# Gesture_rf_controller_v1.net
KiCad netlist of a schematic drawn in EAGLE
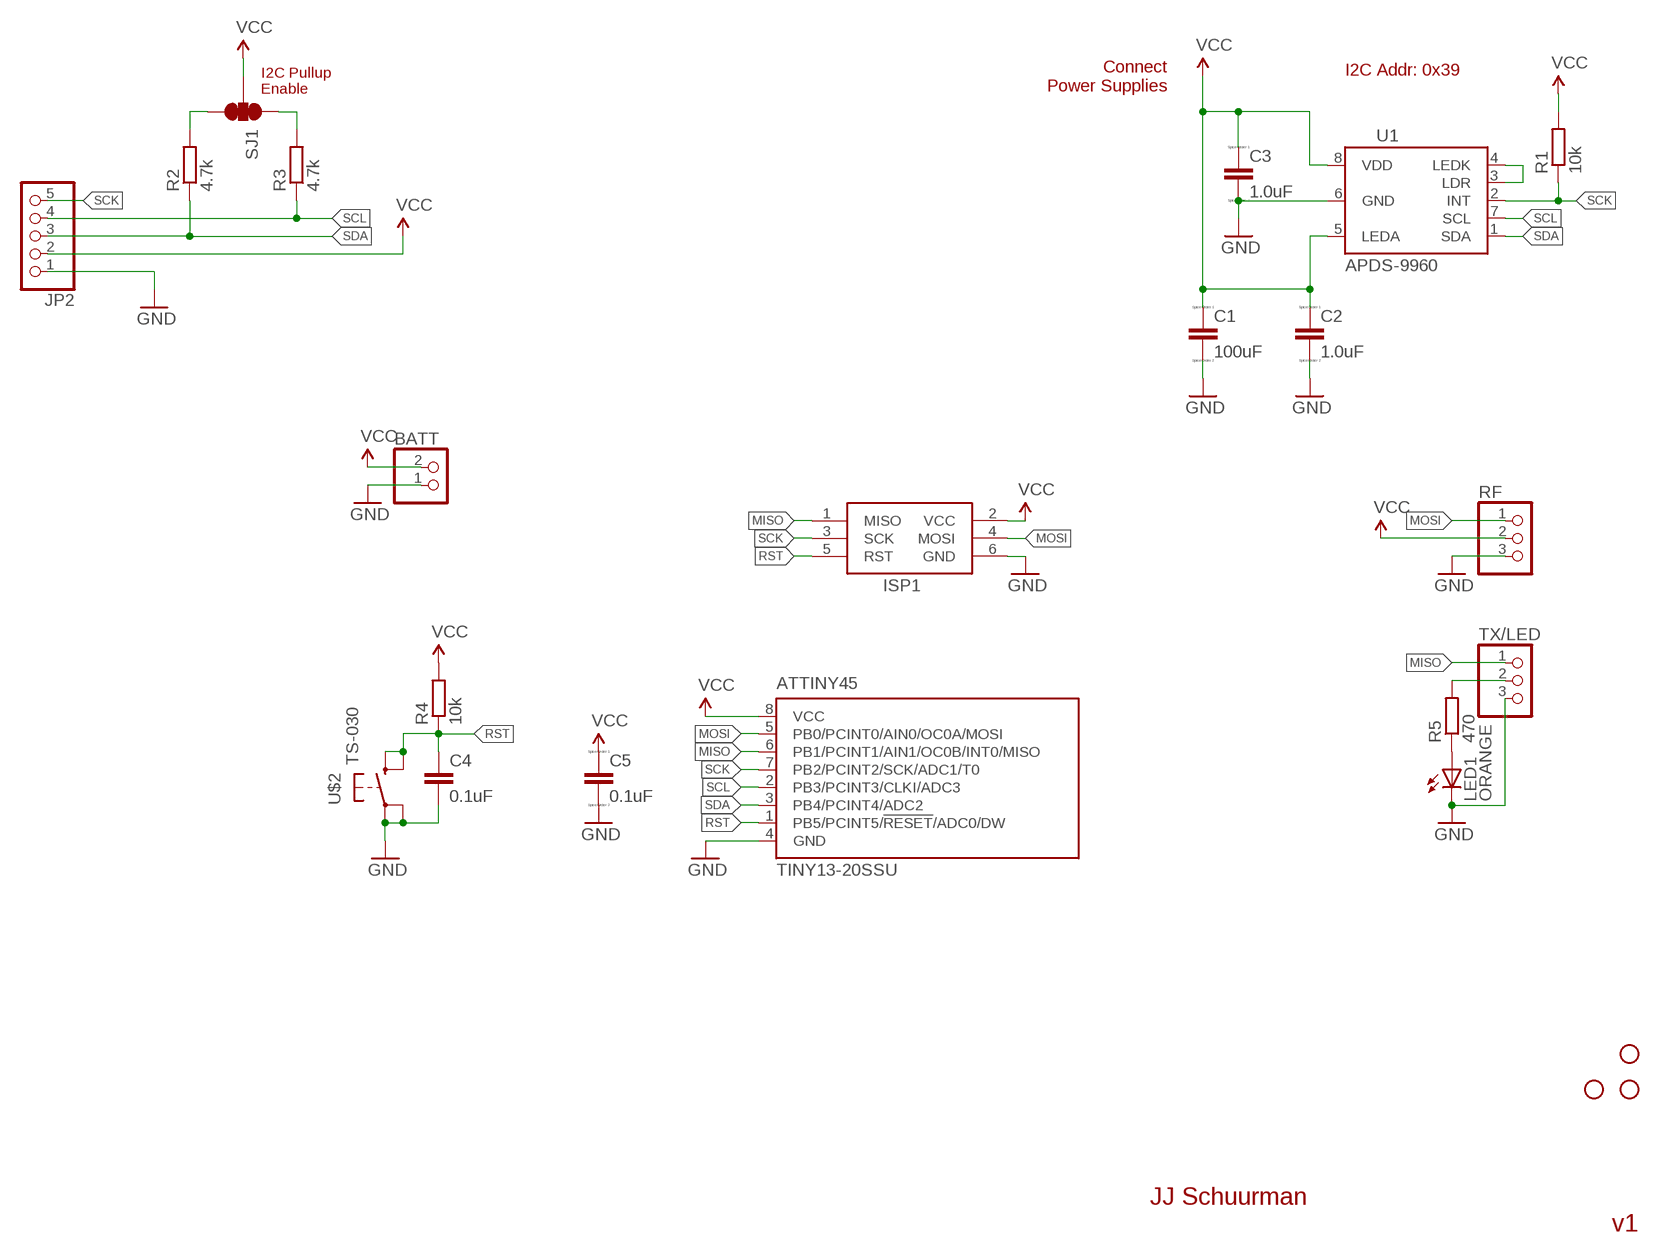
[diagram p0: schematic, sheet 1]

(export (version "E")
  (design (tool "Eeschema 10.0.6"))
  (components
    (comp (ref "ATTINY45")
      (value "TINY13-20SSU")
      (footprint "eagle-import:8S1")
      (fields (field (name "MPN") "ATTINY13-20SSU"))
      (libsource (lib "eagle-import") (part "TINY13SSU-20"))
    )
    (comp (ref "BATT")
      (value "JST_2PIN-THM")
      (footprint "eagle-import:JST-PH-2-THM")
      (libsource (lib "eagle-import") (part "JST_2PIN-THM"))
    )
    (comp (ref "C1")
      (value "100uF")
      (footprint "eagle-import:C0805")
      (libsource (lib "eagle-import") (part "resistor_C-EUC0805"))
    )
    (comp (ref "C2")
      (value "1.0uF")
      (footprint "eagle-import:C0805")
      (libsource (lib "eagle-import") (part "resistor_C-EUC0805"))
    )
    (comp (ref "C3")
      (value "1.0uF")
      (footprint "eagle-import:C0805")
      (libsource (lib "eagle-import") (part "resistor_C-EUC0805"))
    )
    (comp (ref "C4")
      (value "0.1uF")
      (footprint "eagle-import:C1206")
      (libsource (lib "eagle-import") (part "C-EUC1206"))
    )
    (comp (ref "C5")
      (value "0.1uF")
      (footprint "eagle-import:C0805")
      (libsource (lib "eagle-import") (part "resistor_C-EUC0805"))
    )
    (comp (ref "ISP1")
      (value "AVRISP-6")
      (footprint "eagle-import:AVRISP")
      (libsource (lib "eagle-import") (part "AVRISP-6"))
    )
    (comp (ref "JP2")
      (value "PINHD-1X5")
      (footprint "eagle-import:1X05")
      (libsource (lib "eagle-import") (part "PINHD-1X5"))
    )
    (comp (ref "LED1")
      (value "ORANGE")
      (footprint "eagle-import:CHIP-LED0805")
      (libsource (lib "eagle-import") (part "LEDCHIP-LED0805"))
    )
    (comp (ref "R1")
      (value "10k")
      (footprint "eagle-import:R0805")
      (libsource (lib "eagle-import") (part "R-EU_R0805"))
    )
    (comp (ref "R2")
      (value "4.7k")
      (footprint "eagle-import:R1206")
      (libsource (lib "eagle-import") (part "R-EU_R1206"))
    )
    (comp (ref "R3")
      (value "4.7k")
      (footprint "eagle-import:R1206")
      (libsource (lib "eagle-import") (part "R-EU_R1206"))
    )
    (comp (ref "R4")
      (value "10k")
      (footprint "eagle-import:M0805")
      (libsource (lib "eagle-import") (part "R-EU_M0805"))
    )
    (comp (ref "R5")
      (value "470")
      (footprint "eagle-import:R0805")
      (libsource (lib "eagle-import") (part "R-EU_R0805"))
    )
    (comp (ref "RF")
      (value "PINHD-1X3")
      (footprint "eagle-import:1X03")
      (libsource (lib "eagle-import") (part "PINHD-1X3"))
    )
    (comp (ref "SJ1")
      (value "SOLDERJUMPER_2WAYPASTE1&2&3")
      (footprint "eagle-import:SJ_3_PASTE1&2&3")
      (libsource (lib "eagle-import") (part "SOLDERJUMPER_2WAYPASTE1&2&3"))
    )
    (comp (ref "STANDOFF1")
      (value "STAND-OFF")
      (footprint "eagle-import:STAND-OFF")
      (libsource (lib "eagle-import") (part "STAND-OFF"))
    )
    (comp (ref "STANDOFF2")
      (value "STAND-OFF")
      (footprint "eagle-import:STAND-OFF")
      (libsource (lib "eagle-import") (part "STAND-OFF"))
    )
    (comp (ref "STANDOFF4")
      (value "STAND-OFF")
      (footprint "eagle-import:STAND-OFF")
      (libsource (lib "eagle-import") (part "STAND-OFF"))
    )
    (comp (ref "TX/LED")
      (value "PINHD-1X3")
      (footprint "eagle-import:1X03")
      (libsource (lib "eagle-import") (part "PINHD-1X3"))
    )
    (comp (ref "U$2")
      (value "TS-030")
      (footprint "eagle-import:TS-030")
      (libsource (lib "eagle-import") (part "TS-030"))
    )
    (comp (ref "U1")
      (value "APDS-9960")
      (footprint "eagle-import:APDS-9960")
      (libsource (lib "eagle-import") (part "APDS-9960"))
    )
  )
  (nets
    (net (code "1") (name "GND") (class "Default")
      (node (ref "ATTINY45") (pin "4") (pinfunction "GND_4") (pintype "power_in"))
      (node (ref "BATT") (pin "1") (pinfunction "2_1") (pintype "passive"))
      (node (ref "C1") (pin "2") (pinfunction "2_2") (pintype "passive"))
      (node (ref "C2") (pin "2") (pinfunction "2_2") (pintype "passive"))
      (node (ref "C3") (pin "2") (pinfunction "2_2") (pintype "passive"))
      (node (ref "C4") (pin "2") (pinfunction "2_2") (pintype "passive"))
      (node (ref "C5") (pin "2") (pinfunction "2_2") (pintype "passive"))
      (node (ref "ISP1") (pin "6") (pinfunction "GND_6") (pintype "power_in"))
      (node (ref "JP2") (pin "1") (pinfunction "1_1") (pintype "passive"))
      (node (ref "LED1") (pin "C") (pinfunction "C_C") (pintype "passive"))
      (node (ref "RF") (pin "3") (pinfunction "3_3") (pintype "passive"))
      (node (ref "TX/LED") (pin "3") (pinfunction "3_3") (pintype "passive"))
      (node (ref "U$2") (pin "P$2") (pinfunction "1_P$2") (pintype "passive"))
      (node (ref "U$2") (pin "P$3") (pinfunction "2_P$3") (pintype "passive"))
      (node (ref "U1") (pin "6") (pinfunction "GND_6") (pintype "bidirectional"))
    )
    (net (code "2") (name "MISO") (class "Default")
      (node (ref "ATTINY45") (pin "6") (pinfunction "PB1/PCINT1/AIN1/OC0B/INT0/MISO_6") (pintype "bidirectional"))
      (node (ref "ISP1") (pin "1") (pinfunction "MISO_1") (pintype "input"))
      (node (ref "TX/LED") (pin "1") (pinfunction "1_1") (pintype "passive"))
    )
    (net (code "3") (name "MOSI") (class "Default")
      (node (ref "ATTINY45") (pin "5") (pinfunction "PB0/PCINT0/AIN0/OC0A/MOSI_5") (pintype "bidirectional"))
      (node (ref "ISP1") (pin "4") (pinfunction "MOSI_4") (pintype "output"))
      (node (ref "RF") (pin "1") (pinfunction "1_1") (pintype "passive"))
    )
    (net (code "4") (name "Net-(LED1-PadA)") (class "Default")
      (node (ref "LED1") (pin "A") (pinfunction "A_A") (pintype "passive"))
      (node (ref "R5") (pin "1") (pinfunction "1_1") (pintype "passive"))
    )
    (net (code "5") (name "Net-(R2-Pad2)") (class "Default")
      (node (ref "R2") (pin "2") (pinfunction "2_2") (pintype "passive"))
      (node (ref "SJ1") (pin "3") (pinfunction "3_3") (pintype "passive"))
    )
    (net (code "6") (name "Net-(R3-Pad2)") (class "Default")
      (node (ref "R3") (pin "2") (pinfunction "2_2") (pintype "passive"))
      (node (ref "SJ1") (pin "1") (pinfunction "1_1") (pintype "passive"))
    )
    (net (code "7") (name "Net-(R5-Pad2)") (class "Default")
      (node (ref "R5") (pin "2") (pinfunction "2_2") (pintype "passive"))
      (node (ref "TX/LED") (pin "2") (pinfunction "2_2") (pintype "passive"))
    )
    (net (code "8") (name "Net-(U1-LDR)") (class "Default")
      (node (ref "U1") (pin "3") (pinfunction "LDR_3") (pintype "bidirectional"))
      (node (ref "U1") (pin "4") (pinfunction "LEDK_4") (pintype "bidirectional"))
    )
    (net (code "9") (name "RST") (class "Default")
      (node (ref "ATTINY45") (pin "1") (pinfunction "PB5/PCINT5/~{RESET}/ADC0/DW_1") (pintype "bidirectional"))
      (node (ref "C4") (pin "1") (pinfunction "1_1") (pintype "passive"))
      (node (ref "ISP1") (pin "5") (pinfunction "RST_5") (pintype "output"))
      (node (ref "R4") (pin "1") (pinfunction "1_1") (pintype "passive"))
      (node (ref "U$2") (pin "P$1") (pinfunction "3_P$1") (pintype "passive"))
      (node (ref "U$2") (pin "P$4") (pinfunction "4_P$4") (pintype "passive"))
    )
    (net (code "10") (name "SCK") (class "Default")
      (node (ref "ATTINY45") (pin "7") (pinfunction "PB2/PCINT2/SCK/ADC1/T0_7") (pintype "bidirectional"))
      (node (ref "ISP1") (pin "3") (pinfunction "SCK_3") (pintype "output"))
      (node (ref "JP2") (pin "5") (pinfunction "5_5") (pintype "passive"))
      (node (ref "R1") (pin "1") (pinfunction "1_1") (pintype "passive"))
      (node (ref "U1") (pin "2") (pinfunction "INT_2") (pintype "bidirectional"))
    )
    (net (code "11") (name "SCL") (class "Default")
      (node (ref "ATTINY45") (pin "2") (pinfunction "PB3/PCINT3/CLKI/ADC3_2") (pintype "bidirectional"))
      (node (ref "JP2") (pin "4") (pinfunction "4_4") (pintype "passive"))
      (node (ref "R3") (pin "1") (pinfunction "1_1") (pintype "passive"))
      (node (ref "U1") (pin "7") (pinfunction "SCL_7") (pintype "bidirectional"))
    )
    (net (code "12") (name "SDA") (class "Default")
      (node (ref "ATTINY45") (pin "3") (pinfunction "PB4/PCINT4/ADC2_3") (pintype "bidirectional"))
      (node (ref "JP2") (pin "3") (pinfunction "3_3") (pintype "passive"))
      (node (ref "R2") (pin "1") (pinfunction "1_1") (pintype "passive"))
      (node (ref "U1") (pin "1") (pinfunction "SDA_1") (pintype "bidirectional"))
    )
    (net (code "13") (name "VCC") (class "Default")
      (node (ref "ATTINY45") (pin "8") (pinfunction "VCC_8") (pintype "power_in"))
      (node (ref "BATT") (pin "2") (pinfunction "1_2") (pintype "passive"))
      (node (ref "C1") (pin "1") (pinfunction "1_1") (pintype "passive"))
      (node (ref "C2") (pin "1") (pinfunction "1_1") (pintype "passive"))
      (node (ref "C3") (pin "1") (pinfunction "1_1") (pintype "passive"))
      (node (ref "C5") (pin "1") (pinfunction "1_1") (pintype "passive"))
      (node (ref "ISP1") (pin "2") (pinfunction "VCC_2") (pintype "power_in"))
      (node (ref "JP2") (pin "2") (pinfunction "2_2") (pintype "passive"))
      (node (ref "R1") (pin "2") (pinfunction "2_2") (pintype "passive"))
      (node (ref "R4") (pin "2") (pinfunction "2_2") (pintype "passive"))
      (node (ref "RF") (pin "2") (pinfunction "2_2") (pintype "passive"))
      (node (ref "SJ1") (pin "2") (pinfunction "2_2") (pintype "passive"))
      (node (ref "U1") (pin "5") (pinfunction "LEDA_5") (pintype "bidirectional"))
      (node (ref "U1") (pin "8") (pinfunction "VDD_8") (pintype "bidirectional"))
    )
  )
)
